# Power.net
KiCad netlist of a schematic drawn in Altium Designer
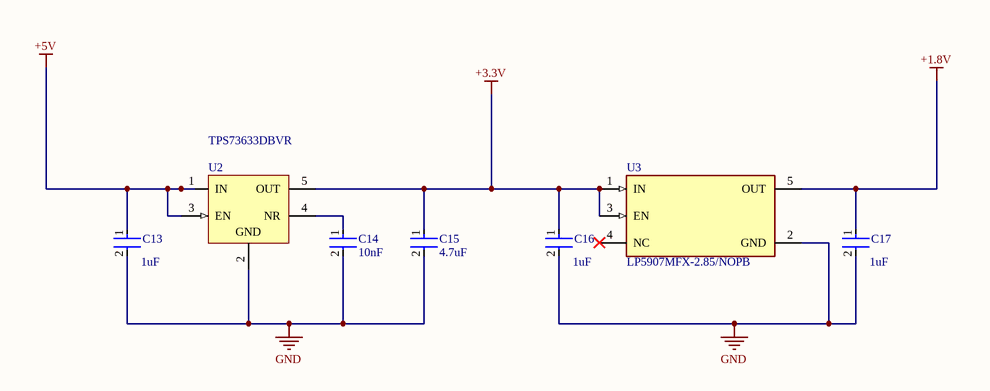
[diagram p0: Power.SchDoc]

(export (version "E")
  (design (tool "Eeschema 10.0.6"))
  (components
    (comp (ref "C13")
      (value "C0805C106K8PACTU")
      (footprint "FP-C0805C-DG-MFG")
      (description "CAP CER 10UF 10V X5R 0805")
      (fields
        (field (name "TOLERANCE") "10%")
        (field (name "MANUFACTURER") "Kemet")
        (field (name "CAPACITANCE") "1uF")
      )
      (libsource (lib "Altium Content Vault") (part "11868f565c42a9108669ba33697ecf6"))
    )
    (comp (ref "C14")
      (value "10nF")
      (footprint "FP-C0805C-DN-MFG")
      (description "CAP CER 10000PF 25V 5% NP0 0805")
      (fields
        (field (name "OCTOPART") "https://octopart.com/c0805c103j3gactu-kemet-12563663")
        (field (name "TOLERANCE") "0.05")
      )
      (libsource (lib "Altium Content Vault") (part "b4654b650e69147ec39a6b967a45e02"))
    )
    (comp (ref "C15")
      (value "4.7uF")
      (footprint "FP-C0805C475K8PACTU-MFG")
      (description "CAP CER 4.7UF 10V X5R 0805")
      (fields (field (name "TOLERANCE") "10%") (field (name "VOLTAGE") "10V"))
      (libsource (lib "Altium Content Vault") (part "e9c51b7dd13d4faca003ae77663ab08"))
    )
    (comp (ref "C16")
      (value "C0805C106K8PACTU")
      (footprint "FP-C0805C-DG-MFG")
      (description "CAP CER 10UF 10V X5R 0805")
      (fields
        (field (name "TOLERANCE") "10%")
        (field (name "MANUFACTURER") "Kemet")
        (field (name "CAPACITANCE") "1uF")
      )
      (libsource (lib "Altium Content Vault") (part "11868f565c42a9108669ba33697ecf6"))
    )
    (comp (ref "C17")
      (value "C0805C106K8PACTU")
      (footprint "FP-C0805C-DG-MFG")
      (description "CAP CER 10UF 10V X5R 0805")
      (fields
        (field (name "TOLERANCE") "10%")
        (field (name "MANUFACTURER") "Kemet")
        (field (name "CAPACITANCE") "1uF")
      )
      (libsource (lib "Altium Content Vault") (part "11868f565c42a9108669ba33697ecf6"))
    )
    (comp (ref "U2")
      (value "TPS73633DBVR")
      (footprint "DBV0005A_L")
      (fields (field (name "MANUFACTURER") "Texas Instruments"))
      (libsource (lib "Altium Content Vault") (part "TI-TPS79NXX-YYSOT5"))
    )
    (comp (ref "U3")
      (value "LP5907MFX-2.85/NOPB")
      (footprint "FP-DBV0005A-IPC_C")
      (description "IC REG LIN 2.85V 250MA SOT23-5")
      (libsource (lib "Altium Content Vault") (part "d086a7f0898e09c792e24704d80cdf4"))
    )
  )
  (nets
    (net (code "1") (name "+1.8V") (class "Default")
      (node (ref "C17") (pin "1") (pinfunction "1_1") (pintype "passive"))
      (node (ref "U3") (pin "5") (pinfunction "OUT_5") (pintype "passive"))
    )
    (net (code "2") (name "+3.3V") (class "Default")
      (node (ref "C15") (pin "1") (pinfunction "1_1") (pintype "passive"))
      (node (ref "C16") (pin "1") (pinfunction "1_1") (pintype "passive"))
      (node (ref "U2") (pin "5") (pinfunction "OUT_5") (pintype "power_in"))
      (node (ref "U3") (pin "1") (pinfunction "IN_1") (pintype "input"))
      (node (ref "U3") (pin "3") (pinfunction "EN_3") (pintype "input"))
    )
    (net (code "3") (name "+5V") (class "Default")
      (node (ref "C13") (pin "1") (pinfunction "1_1") (pintype "passive"))
      (node (ref "U2") (pin "1") (pinfunction "IN_1") (pintype "power_in"))
      (node (ref "U2") (pin "3") (pinfunction "EN_3") (pintype "input"))
    )
    (net (code "4") (name "GND") (class "Default")
      (node (ref "C13") (pin "2") (pinfunction "2_2") (pintype "passive"))
      (node (ref "C14") (pin "2") (pinfunction "2_2") (pintype "passive"))
      (node (ref "C15") (pin "2") (pinfunction "2_2") (pintype "passive"))
      (node (ref "C16") (pin "2") (pinfunction "2_2") (pintype "passive"))
      (node (ref "C17") (pin "2") (pinfunction "2_2") (pintype "passive"))
      (node (ref "U2") (pin "2") (pinfunction "GND_2") (pintype "power_in"))
      (node (ref "U3") (pin "2") (pinfunction "GND_2") (pintype "power_in"))
    )
    (net (code "5") (name "Net-(U2-NR)") (class "Default")
      (node (ref "C14") (pin "1") (pinfunction "1_1") (pintype "passive"))
      (node (ref "U2") (pin "4") (pinfunction "NR_4") (pintype "passive"))
    )
    (net (code "6") (name "unconnected-(U3-NC-Pad4)") (class "Default")
      (node (ref "U3") (pin "4") (pinfunction "NC_4") (pintype "passive+no_connect"))
    )
  )
)
